# dipi_tool.net
KiCad netlist of a schematic drawn in EAGLE
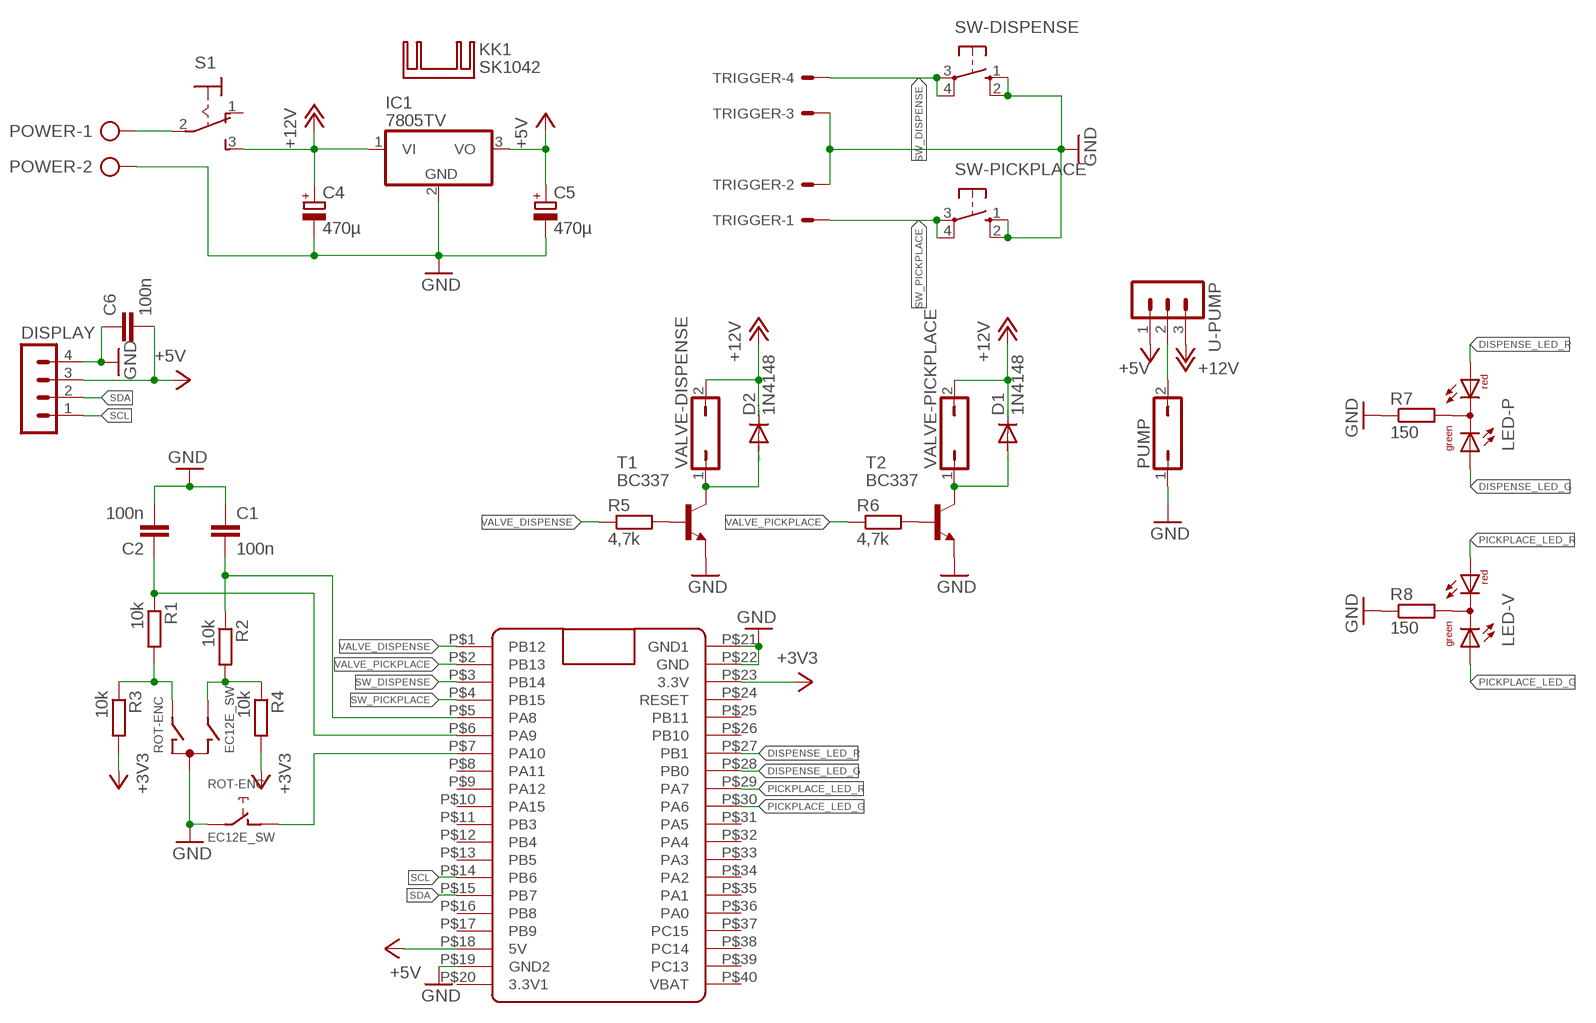
[diagram p0: schematic, sheet 1]

(export (version "E")
  (design (tool "Eeschema 10.0.6"))
  (components
    (comp (ref "C1")
      (value "100n")
      (footprint "eagle-import:C1206")
      (libsource (lib "eagle-import") (part "C-EUC1206"))
    )
    (comp (ref "C2")
      (value "100n")
      (footprint "eagle-import:C1206")
      (libsource (lib "eagle-import") (part "C-EUC1206"))
    )
    (comp (ref "C4")
      (value "470µ")
      (footprint "eagle-import:E3,5-10")
      (libsource (lib "eagle-import") (part "CPOL-EUE3.5-10"))
    )
    (comp (ref "C5")
      (value "470µ")
      (footprint "eagle-import:E2,5-7")
      (libsource (lib "eagle-import") (part "CPOL-EUE2.5-7"))
    )
    (comp (ref "C6")
      (value "100n")
      (footprint "eagle-import:C1206")
      (libsource (lib "eagle-import") (part "C-EUC1206"))
    )
    (comp (ref "D1")
      (value "1N4148")
      (footprint "eagle-import:DO35-7")
      (libsource (lib "eagle-import") (part "1N4148DO35-7"))
    )
    (comp (ref "D2")
      (value "1N4148")
      (footprint "eagle-import:DO35-7")
      (libsource (lib "eagle-import") (part "1N4148DO35-7"))
    )
    (comp (ref "DISPLAY")
      (value "MA04-1")
      (footprint "eagle-import:MA04-1")
      (libsource (lib "eagle-import") (part "MA04-1"))
    )
    (comp (ref "IC1")
      (value "7805TV")
      (footprint "eagle-import:TO220V")
      (libsource (lib "eagle-import") (part "78TV05"))
    )
    (comp (ref "KK1")
      (value "SK1042")
      (footprint "eagle-import:CUSTOM1-PAD")
      (libsource (lib "eagle-import") (part "SK1042"))
    )
    (comp (ref "LED-P")
      (value "DUOLED-RG-C\"")
      (footprint "eagle-import:DUOLED-C-3MM")
      (libsource (lib "eagle-import") (part "DUOLED-RG-C{dblquote}"))
    )
    (comp (ref "LED-V")
      (value "DUOLED-RG-C\"")
      (footprint "eagle-import:DUOLED-C-3MM")
      (libsource (lib "eagle-import") (part "DUOLED-RG-C{dblquote}"))
    )
    (comp (ref "POWER")
      (value "AK500/2")
      (footprint "eagle-import:AK500_2")
      (libsource (lib "eagle-import") (part "AK500/2"))
    )
    (comp (ref "PUMP")
      (value "JP1Q")
      (footprint "eagle-import:JP1")
      (libsource (lib "eagle-import") (part "JP1Q"))
    )
    (comp (ref "R1")
      (value "10k")
      (footprint "eagle-import:R1206")
      (libsource (lib "eagle-import") (part "R-EU_R1206"))
    )
    (comp (ref "R2")
      (value "10k")
      (footprint "eagle-import:R1206")
      (libsource (lib "eagle-import") (part "R-EU_R1206"))
    )
    (comp (ref "R3")
      (value "10k")
      (footprint "eagle-import:R1206")
      (libsource (lib "eagle-import") (part "R-EU_R1206"))
    )
    (comp (ref "R4")
      (value "10k")
      (footprint "eagle-import:R1206")
      (libsource (lib "eagle-import") (part "R-EU_R1206"))
    )
    (comp (ref "R5")
      (value "4,7k")
      (footprint "eagle-import:0204V")
      (libsource (lib "eagle-import") (part "R-EU_0204/2V"))
    )
    (comp (ref "R6")
      (value "4,7k")
      (footprint "eagle-import:0204V")
      (libsource (lib "eagle-import") (part "R-EU_0204/2V"))
    )
    (comp (ref "R7")
      (value "150")
      (footprint "eagle-import:0204V")
      (libsource (lib "eagle-import") (part "R-EU_0204/2V"))
    )
    (comp (ref "R8")
      (value "150")
      (footprint "eagle-import:0204V")
      (libsource (lib "eagle-import") (part "R-EU_0204/2V"))
    )
    (comp (ref "ROT-ENC")
      (value "EC12E_SW")
      (footprint "eagle-import:ALPS_EC12E_SW")
      (fields (field (name "MPN") "EC12E2424407"))
      (libsource (lib "eagle-import") (part "EC12E_SW"))
    )
    (comp (ref "S1")
      (value "M9040P")
      (footprint "eagle-import:M9040P")
      (libsource (lib "eagle-import") (part "M9040P"))
    )
    (comp (ref "SW-DISPENSE")
      (value "10-XX")
      (footprint "eagle-import:B3F-10XX")
      (fields (field (name "MPN") "B3F-1000"))
      (libsource (lib "eagle-import") (part "10-XX"))
    )
    (comp (ref "SW-PICKPLACE")
      (value "10-XX")
      (footprint "eagle-import:B3F-10XX")
      (fields (field (name "MPN") "B3F-1000"))
      (libsource (lib "eagle-import") (part "10-XX"))
    )
    (comp (ref "T1")
      (value "BC337")
      (footprint "eagle-import:TO92")
      (libsource (lib "eagle-import") (part "BC337"))
    )
    (comp (ref "T2")
      (value "BC337")
      (footprint "eagle-import:TO92")
      (libsource (lib "eagle-import") (part "BC337"))
    )
    (comp (ref "TRIGGER")
      (value "22-27-2041-04")
      (footprint "eagle-import:6410-04")
      (libsource (lib "eagle-import") (part "22-?-0427-2041"))
    )
    (comp (ref "U$1")
      (value "BLUE_PILL")
      (footprint "eagle-import:BLUE_PILL")
      (libsource (lib "eagle-import") (part "BLUE_PILL"))
    )
    (comp (ref "U-PUMP")
      (value "MA03-1")
      (footprint "eagle-import:MA03-1")
      (libsource (lib "eagle-import") (part "MA03-1"))
    )
    (comp (ref "VALVE-DISPENSE")
      (value "JP1Q")
      (footprint "eagle-import:JP1")
      (libsource (lib "eagle-import") (part "JP1Q"))
    )
    (comp (ref "VALVE-PICKPLACE")
      (value "JP1Q")
      (footprint "eagle-import:JP1")
      (libsource (lib "eagle-import") (part "JP1Q"))
    )
  )
  (nets
    (net (code "1") (name "+3V3") (class "Default")
      (node (ref "R3") (pin "2") (pinfunction "2_2") (pintype "passive"))
      (node (ref "R4") (pin "2") (pinfunction "2_2") (pintype "passive"))
      (node (ref "U$1") (pin "P$23") (pinfunction "3.3V_P$23") (pintype "bidirectional"))
    )
    (net (code "2") (name "+5V") (class "Default")
      (node (ref "C5") (pin "+") (pinfunction "+_+") (pintype "passive"))
      (node (ref "C6") (pin "2") (pinfunction "2_2") (pintype "passive"))
      (node (ref "DISPLAY") (pin "3") (pinfunction "3_3") (pintype "passive"))
      (node (ref "IC1") (pin "3") (pinfunction "VO_3") (pintype "passive"))
      (node (ref "U$1") (pin "P$18") (pinfunction "5V_P$18") (pintype "bidirectional"))
      (node (ref "U-PUMP") (pin "1") (pinfunction "1_1") (pintype "passive"))
    )
    (net (code "3") (name "+12V") (class "Default")
      (node (ref "C4") (pin "+") (pinfunction "+_+") (pintype "passive"))
      (node (ref "D1") (pin "C") (pinfunction "C_C") (pintype "passive"))
      (node (ref "D2") (pin "C") (pinfunction "C_C") (pintype "passive"))
      (node (ref "IC1") (pin "1") (pinfunction "VI_1") (pintype "input"))
      (node (ref "S1") (pin "3") (pinfunction "S_3") (pintype "passive"))
      (node (ref "U-PUMP") (pin "3") (pinfunction "3_3") (pintype "passive"))
      (node (ref "VALVE-DISPENSE") (pin "2") (pinfunction "2_2") (pintype "passive"))
      (node (ref "VALVE-PICKPLACE") (pin "2") (pinfunction "2_2") (pintype "passive"))
    )
    (net (code "4") (name "DISPENSE_LED_G") (class "Default")
      (node (ref "LED-P") (pin "1") (pinfunction "AG_1") (pintype "passive"))
      (node (ref "U$1") (pin "P$28") (pinfunction "PB0_P$28") (pintype "bidirectional"))
    )
    (net (code "5") (name "DISPENSE_LED_R") (class "Default")
      (node (ref "LED-P") (pin "3") (pinfunction "AR_3") (pintype "passive"))
      (node (ref "U$1") (pin "P$27") (pinfunction "PB1_P$27") (pintype "bidirectional"))
    )
    (net (code "6") (name "GND") (class "Default")
      (node (ref "C1") (pin "1") (pinfunction "1_1") (pintype "passive"))
      (node (ref "C2") (pin "2") (pinfunction "2_2") (pintype "passive"))
      (node (ref "C4") (pin "-") (pinfunction "-_-") (pintype "passive"))
      (node (ref "C5") (pin "-") (pinfunction "-_-") (pintype "passive"))
      (node (ref "C6") (pin "1") (pinfunction "1_1") (pintype "passive"))
      (node (ref "DISPLAY") (pin "4") (pinfunction "4_4") (pintype "passive"))
      (node (ref "IC1") (pin "2") (pinfunction "GND_2") (pintype "passive"))
      (node (ref "POWER") (pin "2") (pinfunction "KL_2") (pintype "passive"))
      (node (ref "PUMP") (pin "1") (pinfunction "1_1") (pintype "passive"))
      (node (ref "R7") (pin "1") (pinfunction "1_1") (pintype "passive"))
      (node (ref "R8") (pin "1") (pinfunction "1_1") (pintype "passive"))
      (node (ref "ROT-ENC") (pin "C") (pinfunction "C_C") (pintype "passive"))
      (node (ref "ROT-ENC") (pin "E") (pinfunction "2_E") (pintype "passive"))
      (node (ref "SW-DISPENSE") (pin "1") (pinfunction "S_1") (pintype "passive"))
      (node (ref "SW-DISPENSE") (pin "2") (pinfunction "S1_2") (pintype "passive"))
      (node (ref "SW-PICKPLACE") (pin "1") (pinfunction "S_1") (pintype "passive"))
      (node (ref "SW-PICKPLACE") (pin "2") (pinfunction "S1_2") (pintype "passive"))
      (node (ref "T1") (pin "1") (pinfunction "E_1") (pintype "passive"))
      (node (ref "T2") (pin "1") (pinfunction "E_1") (pintype "passive"))
      (node (ref "TRIGGER") (pin "2") (pinfunction "S_2") (pintype "passive"))
      (node (ref "TRIGGER") (pin "3") (pinfunction "S_3") (pintype "passive"))
      (node (ref "U$1") (pin "P$19") (pinfunction "GND2_P$19") (pintype "bidirectional"))
      (node (ref "U$1") (pin "P$21") (pinfunction "GND1_P$21") (pintype "power_in"))
      (node (ref "U$1") (pin "P$22") (pinfunction "GND_P$22") (pintype "bidirectional"))
    )
    (net (code "7") (name "Net-(LED-P-C)") (class "Default")
      (node (ref "LED-P") (pin "2") (pinfunction "C_2") (pintype "passive"))
      (node (ref "R7") (pin "2") (pinfunction "2_2") (pintype "passive"))
    )
    (net (code "8") (name "Net-(LED-V-C)") (class "Default")
      (node (ref "LED-V") (pin "2") (pinfunction "C_2") (pintype "passive"))
      (node (ref "R8") (pin "2") (pinfunction "2_2") (pintype "passive"))
    )
    (net (code "9") (name "Net-(POWERA-KL)") (class "Default")
      (node (ref "POWER") (pin "1") (pinfunction "KL_1") (pintype "passive"))
      (node (ref "S1") (pin "2") (pinfunction "P_2") (pintype "passive"))
    )
    (net (code "10") (name "Net-(PUMP-Pad2)") (class "Default")
      (node (ref "PUMP") (pin "2") (pinfunction "2_2") (pintype "passive"))
      (node (ref "U-PUMP") (pin "2") (pinfunction "2_2") (pintype "passive"))
    )
    (net (code "11") (name "Net-(R1-Pad2)") (class "Default")
      (node (ref "R1") (pin "2") (pinfunction "2_2") (pintype "passive"))
      (node (ref "R3") (pin "1") (pinfunction "1_1") (pintype "passive"))
      (node (ref "ROT-ENC") (pin "A") (pinfunction "A_A") (pintype "passive"))
    )
    (net (code "12") (name "Net-(R2-Pad2)") (class "Default")
      (node (ref "R2") (pin "2") (pinfunction "2_2") (pintype "passive"))
      (node (ref "R4") (pin "1") (pinfunction "1_1") (pintype "passive"))
      (node (ref "ROT-ENC") (pin "B") (pinfunction "B_B") (pintype "passive"))
    )
    (net (code "13") (name "Net-(ROT-ENCB-1)") (class "Default")
      (node (ref "ROT-ENC") (pin "D") (pinfunction "1_D") (pintype "passive"))
      (node (ref "U$1") (pin "P$7") (pinfunction "PA10_P$7") (pintype "bidirectional"))
    )
    (net (code "14") (name "Net-(T1-B)") (class "Default")
      (node (ref "R5") (pin "2") (pinfunction "2_2") (pintype "passive"))
      (node (ref "T1") (pin "2") (pinfunction "B_2") (pintype "passive"))
    )
    (net (code "15") (name "Net-(T1-C)") (class "Default")
      (node (ref "D2") (pin "A") (pinfunction "A_A") (pintype "passive"))
      (node (ref "T1") (pin "3") (pinfunction "C_3") (pintype "passive"))
      (node (ref "VALVE-DISPENSE") (pin "1") (pinfunction "1_1") (pintype "passive"))
    )
    (net (code "16") (name "Net-(T2-B)") (class "Default")
      (node (ref "R6") (pin "2") (pinfunction "2_2") (pintype "passive"))
      (node (ref "T2") (pin "2") (pinfunction "B_2") (pintype "passive"))
    )
    (net (code "17") (name "Net-(T2-C)") (class "Default")
      (node (ref "D1") (pin "A") (pinfunction "A_A") (pintype "passive"))
      (node (ref "T2") (pin "3") (pinfunction "C_3") (pintype "passive"))
      (node (ref "VALVE-PICKPLACE") (pin "1") (pinfunction "1_1") (pintype "passive"))
    )
    (net (code "18") (name "Net-(U$1-PA8)") (class "Default")
      (node (ref "C1") (pin "2") (pinfunction "2_2") (pintype "passive"))
      (node (ref "R2") (pin "1") (pinfunction "1_1") (pintype "passive"))
      (node (ref "U$1") (pin "P$5") (pinfunction "PA8_P$5") (pintype "bidirectional"))
    )
    (net (code "19") (name "Net-(U$1-PA9)") (class "Default")
      (node (ref "C2") (pin "1") (pinfunction "1_1") (pintype "passive"))
      (node (ref "R1") (pin "1") (pinfunction "1_1") (pintype "passive"))
      (node (ref "U$1") (pin "P$6") (pinfunction "PA9_P$6") (pintype "bidirectional"))
    )
    (net (code "20") (name "PICKPLACE_LED_G") (class "Default")
      (node (ref "LED-V") (pin "1") (pinfunction "AG_1") (pintype "passive"))
      (node (ref "U$1") (pin "P$30") (pinfunction "PA6_P$30") (pintype "bidirectional"))
    )
    (net (code "21") (name "PICKPLACE_LED_R") (class "Default")
      (node (ref "LED-V") (pin "3") (pinfunction "AR_3") (pintype "passive"))
      (node (ref "U$1") (pin "P$29") (pinfunction "PA7_P$29") (pintype "bidirectional"))
    )
    (net (code "22") (name "SCL") (class "Default")
      (node (ref "DISPLAY") (pin "1") (pinfunction "1_1") (pintype "passive"))
      (node (ref "U$1") (pin "P$14") (pinfunction "PB6_P$14") (pintype "bidirectional"))
    )
    (net (code "23") (name "SDA") (class "Default")
      (node (ref "DISPLAY") (pin "2") (pinfunction "2_2") (pintype "passive"))
      (node (ref "U$1") (pin "P$15") (pinfunction "PB7_P$15") (pintype "bidirectional"))
    )
    (net (code "24") (name "SW_DISPENSE") (class "Default")
      (node (ref "SW-DISPENSE") (pin "3") (pinfunction "P_3") (pintype "passive"))
      (node (ref "SW-DISPENSE") (pin "4") (pinfunction "P1_4") (pintype "passive"))
      (node (ref "TRIGGER") (pin "4") (pinfunction "S_4") (pintype "passive"))
      (node (ref "U$1") (pin "P$3") (pinfunction "PB14_P$3") (pintype "bidirectional"))
    )
    (net (code "25") (name "SW_PICKPLACE") (class "Default")
      (node (ref "SW-PICKPLACE") (pin "3") (pinfunction "P_3") (pintype "passive"))
      (node (ref "SW-PICKPLACE") (pin "4") (pinfunction "P1_4") (pintype "passive"))
      (node (ref "TRIGGER") (pin "1") (pinfunction "S_1") (pintype "passive"))
      (node (ref "U$1") (pin "P$4") (pinfunction "PB15_P$4") (pintype "bidirectional"))
    )
    (net (code "26") (name "VALVE_DISPENSE") (class "Default")
      (node (ref "R5") (pin "1") (pinfunction "1_1") (pintype "passive"))
      (node (ref "U$1") (pin "P$1") (pinfunction "PB12_P$1") (pintype "bidirectional"))
    )
    (net (code "27") (name "VALVE_PICKPLACE") (class "Default")
      (node (ref "R6") (pin "1") (pinfunction "1_1") (pintype "passive"))
      (node (ref "U$1") (pin "P$2") (pinfunction "PB13_P$2") (pintype "bidirectional"))
    )
    (net (code "28") (name "unconnected-(S1-O-Pad1)") (class "Default")
      (node (ref "S1") (pin "1") (pinfunction "O_1") (pintype "passive"))
    )
    (net (code "29") (name "unconnected-(U$1-3.3V1-PadP$20)") (class "Default")
      (node (ref "U$1") (pin "P$20") (pinfunction "3.3V1_P$20") (pintype "bidirectional"))
    )
    (net (code "30") (name "unconnected-(U$1-PA0-PadP$36)") (class "Default")
      (node (ref "U$1") (pin "P$36") (pinfunction "PA0_P$36") (pintype "bidirectional"))
    )
    (net (code "31") (name "unconnected-(U$1-PA1-PadP$35)") (class "Default")
      (node (ref "U$1") (pin "P$35") (pinfunction "PA1_P$35") (pintype "bidirectional"))
    )
    (net (code "32") (name "unconnected-(U$1-PA2-PadP$34)") (class "Default")
      (node (ref "U$1") (pin "P$34") (pinfunction "PA2_P$34") (pintype "bidirectional"))
    )
    (net (code "33") (name "unconnected-(U$1-PA3-PadP$33)") (class "Default")
      (node (ref "U$1") (pin "P$33") (pinfunction "PA3_P$33") (pintype "bidirectional"))
    )
    (net (code "34") (name "unconnected-(U$1-PA4-PadP$32)") (class "Default")
      (node (ref "U$1") (pin "P$32") (pinfunction "PA4_P$32") (pintype "bidirectional"))
    )
    (net (code "35") (name "unconnected-(U$1-PA5-PadP$31)") (class "Default")
      (node (ref "U$1") (pin "P$31") (pinfunction "PA5_P$31") (pintype "bidirectional"))
    )
    (net (code "36") (name "unconnected-(U$1-PA11-PadP$8)") (class "Default")
      (node (ref "U$1") (pin "P$8") (pinfunction "PA11_P$8") (pintype "bidirectional"))
    )
    (net (code "37") (name "unconnected-(U$1-PA12-PadP$9)") (class "Default")
      (node (ref "U$1") (pin "P$9") (pinfunction "PA12_P$9") (pintype "bidirectional"))
    )
    (net (code "38") (name "unconnected-(U$1-PA15-PadP$10)") (class "Default")
      (node (ref "U$1") (pin "P$10") (pinfunction "PA15_P$10") (pintype "bidirectional"))
    )
    (net (code "39") (name "unconnected-(U$1-PB3-PadP$11)") (class "Default")
      (node (ref "U$1") (pin "P$11") (pinfunction "PB3_P$11") (pintype "bidirectional"))
    )
    (net (code "40") (name "unconnected-(U$1-PB4-PadP$12)") (class "Default")
      (node (ref "U$1") (pin "P$12") (pinfunction "PB4_P$12") (pintype "bidirectional"))
    )
    (net (code "41") (name "unconnected-(U$1-PB5-PadP$13)") (class "Default")
      (node (ref "U$1") (pin "P$13") (pinfunction "PB5_P$13") (pintype "bidirectional"))
    )
    (net (code "42") (name "unconnected-(U$1-PB8-PadP$16)") (class "Default")
      (node (ref "U$1") (pin "P$16") (pinfunction "PB8_P$16") (pintype "bidirectional"))
    )
    (net (code "43") (name "unconnected-(U$1-PB9-PadP$17)") (class "Default")
      (node (ref "U$1") (pin "P$17") (pinfunction "PB9_P$17") (pintype "bidirectional"))
    )
    (net (code "44") (name "unconnected-(U$1-PB10-PadP$26)") (class "Default")
      (node (ref "U$1") (pin "P$26") (pinfunction "PB10_P$26") (pintype "bidirectional"))
    )
    (net (code "45") (name "unconnected-(U$1-PB11-PadP$25)") (class "Default")
      (node (ref "U$1") (pin "P$25") (pinfunction "PB11_P$25") (pintype "bidirectional"))
    )
    (net (code "46") (name "unconnected-(U$1-PC13-PadP$39)") (class "Default")
      (node (ref "U$1") (pin "P$39") (pinfunction "PC13_P$39") (pintype "bidirectional"))
    )
    (net (code "47") (name "unconnected-(U$1-PC14-PadP$38)") (class "Default")
      (node (ref "U$1") (pin "P$38") (pinfunction "PC14_P$38") (pintype "bidirectional"))
    )
    (net (code "48") (name "unconnected-(U$1-PC15-PadP$37)") (class "Default")
      (node (ref "U$1") (pin "P$37") (pinfunction "PC15_P$37") (pintype "bidirectional"))
    )
    (net (code "49") (name "unconnected-(U$1-RESET-PadP$24)") (class "Default")
      (node (ref "U$1") (pin "P$24") (pinfunction "RESET_P$24") (pintype "bidirectional"))
    )
    (net (code "50") (name "unconnected-(U$1-VBAT-PadP$40)") (class "Default")
      (node (ref "U$1") (pin "P$40") (pinfunction "VBAT_P$40") (pintype "bidirectional"))
    )
  )
)
